# gyorsulasmero.net
KiCad netlist of a schematic drawn in Altium Designer
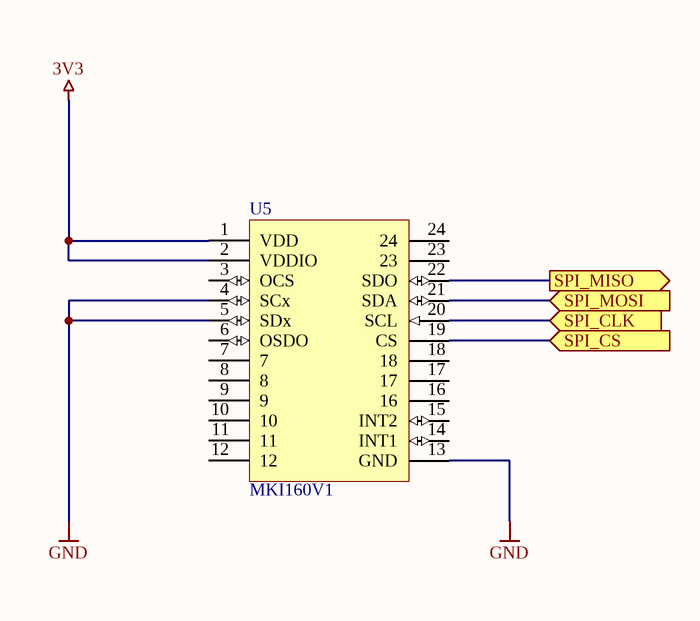
[diagram p0: gyorsulasmero.SchDoc]

(export (version "E")
  (design (tool "Eeschema 10.0.6"))
  (components
    (comp (ref "U5")
      (value "MKI160V1")
      (footprint "FP_DIL24")
      (description "LSM6DS3 inertial module adapter")
      (libsource (lib "hallglib") (part "MKI160V1"))
    )
  )
  (nets
    (net (code "1") (name "/SPI_CLK") (class "Default")
      (node (ref "U5") (pin "20") (pinfunction "SCL_20") (pintype "input"))
    )
    (net (code "2") (name "/SPI_CS") (class "Default")
      (node (ref "U5") (pin "19") (pinfunction "CS_19") (pintype "passive"))
    )
    (net (code "3") (name "/SPI_MISO") (class "Default")
      (node (ref "U5") (pin "22") (pinfunction "SDO_22") (pintype "bidirectional"))
    )
    (net (code "4") (name "/SPI_MOSI") (class "Default")
      (node (ref "U5") (pin "21") (pinfunction "SDA_21") (pintype "bidirectional"))
    )
    (net (code "5") (name "3V3") (class "Default")
      (node (ref "U5") (pin "1") (pinfunction "VDD_1") (pintype "power_in"))
      (node (ref "U5") (pin "2") (pinfunction "VDDIO_2") (pintype "power_in"))
    )
    (net (code "6") (name "GND") (class "Default")
      (node (ref "U5") (pin "13") (pinfunction "GND_13") (pintype "power_in"))
      (node (ref "U5") (pin "4") (pinfunction "SCx_4") (pintype "bidirectional"))
      (node (ref "U5") (pin "5") (pinfunction "SDx_5") (pintype "bidirectional"))
    )
    (net (code "7") (name "unconnected-(U5-INT1-Pad14)") (class "Default")
      (node (ref "U5") (pin "14") (pinfunction "INT1_14") (pintype "bidirectional"))
    )
    (net (code "8") (name "unconnected-(U5-INT2-Pad15)") (class "Default")
      (node (ref "U5") (pin "15") (pinfunction "INT2_15") (pintype "bidirectional"))
    )
    (net (code "9") (name "unconnected-(U5-OCS-Pad3)") (class "Default")
      (node (ref "U5") (pin "3") (pinfunction "OCS_3") (pintype "bidirectional"))
    )
    (net (code "10") (name "unconnected-(U5-OSDO-Pad6)") (class "Default")
      (node (ref "U5") (pin "6") (pinfunction "OSDO_6") (pintype "bidirectional"))
    )
    (net (code "11") (name "unconnected-(U5-Pad7)") (class "Default")
      (node (ref "U5") (pin "7") (pinfunction "7_7") (pintype "passive"))
    )
    (net (code "12") (name "unconnected-(U5-Pad8)") (class "Default")
      (node (ref "U5") (pin "8") (pinfunction "8_8") (pintype "passive"))
    )
    (net (code "13") (name "unconnected-(U5-Pad9)") (class "Default")
      (node (ref "U5") (pin "9") (pinfunction "9_9") (pintype "passive"))
    )
    (net (code "14") (name "unconnected-(U5-Pad10)") (class "Default")
      (node (ref "U5") (pin "10") (pinfunction "10_10") (pintype "passive"))
    )
    (net (code "15") (name "unconnected-(U5-Pad11)") (class "Default")
      (node (ref "U5") (pin "11") (pinfunction "11_11") (pintype "passive"))
    )
    (net (code "16") (name "unconnected-(U5-Pad12)") (class "Default")
      (node (ref "U5") (pin "12") (pinfunction "12_12") (pintype "passive"))
    )
    (net (code "17") (name "unconnected-(U5-Pad16)") (class "Default")
      (node (ref "U5") (pin "16") (pinfunction "16_16") (pintype "passive"))
    )
    (net (code "18") (name "unconnected-(U5-Pad17)") (class "Default")
      (node (ref "U5") (pin "17") (pinfunction "17_17") (pintype "passive"))
    )
    (net (code "19") (name "unconnected-(U5-Pad18)") (class "Default")
      (node (ref "U5") (pin "18") (pinfunction "18_18") (pintype "passive"))
    )
    (net (code "20") (name "unconnected-(U5-Pad23)") (class "Default")
      (node (ref "U5") (pin "23") (pinfunction "23_23") (pintype "passive"))
    )
    (net (code "21") (name "unconnected-(U5-Pad24)") (class "Default")
      (node (ref "U5") (pin "24") (pinfunction "24_24") (pintype "passive"))
    )
  )
)
